# pedalElectricalDrawings.net
KiCad netlist of a schematic drawn in EAGLE
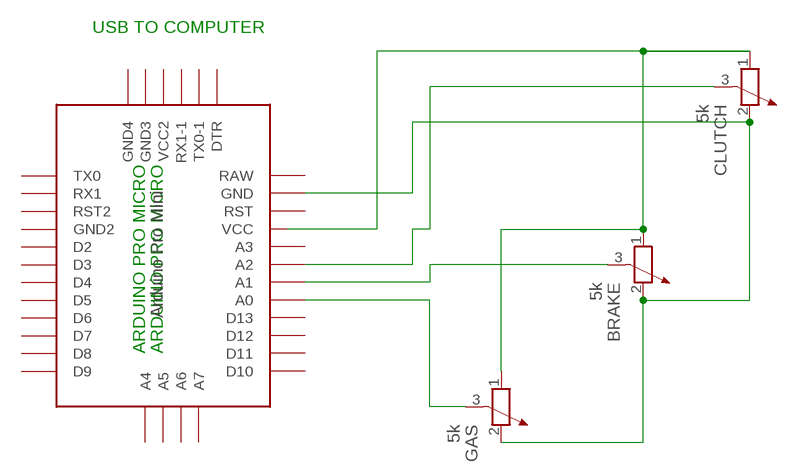
[diagram p0: schematic, sheet 1]

(export (version "E")
  (design (tool "Eeschema 10.0.6"))
  (components
    (comp (ref "BRAKE")
      (value "5k")
      (footprint "eagle-import:PT-10")
      (libsource (lib "eagle-import") (part "POTENTIOMETER_PT-10"))
    )
    (comp (ref "CLUTCH")
      (value "5k")
      (footprint "eagle-import:PT-10")
      (libsource (lib "eagle-import") (part "POTENTIOMETER_PT-10"))
    )
    (comp (ref "GAS")
      (value "5k")
      (footprint "eagle-import:PT-10")
      (libsource (lib "eagle-import") (part "POTENTIOMETER_PT-10"))
    )
    (comp (ref "U$1")
      (value "PRO-MINI")
      (footprint "eagle-import:PRO-MINI")
      (libsource (lib "eagle-import") (part "PRO-MINI"))
    )
  )
  (nets
    (net (code "1") (name "/RAW") (class "Default")
      (node (ref "U$1") (pin "RAW") (pinfunction "RAW_RAW") (pintype "power_in"))
    )
    (net (code "2") (name "Net-(BRAKE-Pad1)") (class "Default")
      (node (ref "BRAKE") (pin "1") (pinfunction "1_1") (pintype "passive"))
      (node (ref "CLUTCH") (pin "1") (pinfunction "1_1") (pintype "passive"))
      (node (ref "GAS") (pin "1") (pinfunction "1_1") (pintype "passive"))
    )
    (net (code "3") (name "Net-(BRAKE-Pad2)") (class "Default")
      (node (ref "BRAKE") (pin "2") (pinfunction "2_2") (pintype "passive"))
      (node (ref "CLUTCH") (pin "2") (pinfunction "2_2") (pintype "passive"))
      (node (ref "GAS") (pin "2") (pinfunction "2_2") (pintype "passive"))
      (node (ref "U$1") (pin "GND") (pinfunction "GND_GND") (pintype "input"))
    )
    (net (code "4") (name "Net-(BRAKE-Pad3)") (class "Default")
      (node (ref "BRAKE") (pin "3") (pinfunction "3_3") (pintype "passive"))
      (node (ref "U$1") (pin "A1") (pinfunction "A1_A1") (pintype "bidirectional"))
    )
    (net (code "5") (name "Net-(CLUTCH-Pad3)") (class "Default")
      (node (ref "CLUTCH") (pin "3") (pinfunction "3_3") (pintype "passive"))
      (node (ref "U$1") (pin "A2") (pinfunction "A2_A2") (pintype "bidirectional"))
    )
    (net (code "6") (name "Net-(GAS-Pad3)") (class "Default")
      (node (ref "GAS") (pin "3") (pinfunction "3_3") (pintype "passive"))
      (node (ref "U$1") (pin "A0") (pinfunction "A0_A0") (pintype "bidirectional"))
    )
    (net (code "7") (name "unconnected-(U$1-GND2-PadGND1)") (class "Default")
      (node (ref "U$1") (pin "GND1") (pinfunction "GND2_GND1") (pintype "bidirectional"))
    )
    (net (code "8") (name "unconnected-(U$1-GND4-PadGND2)") (class "Default")
      (node (ref "U$1") (pin "GND2") (pinfunction "GND4_GND2") (pintype "bidirectional"))
    )
    (net (code "9") (name "unconnected-(U$1-PadA3)") (class "Default")
      (node (ref "U$1") (pin "A3") (pinfunction "A3_A3") (pintype "bidirectional"))
    )
    (net (code "10") (name "unconnected-(U$1-PadA4)") (class "Default")
      (node (ref "U$1") (pin "A4") (pinfunction "A4_A4") (pintype "bidirectional"))
    )
    (net (code "11") (name "unconnected-(U$1-PadA5)") (class "Default")
      (node (ref "U$1") (pin "A5") (pinfunction "A5_A5") (pintype "bidirectional"))
    )
    (net (code "12") (name "unconnected-(U$1-PadA6)") (class "Default")
      (node (ref "U$1") (pin "A6") (pinfunction "A6_A6") (pintype "bidirectional"))
    )
    (net (code "13") (name "unconnected-(U$1-PadA7)") (class "Default")
      (node (ref "U$1") (pin "A7") (pinfunction "A7_A7") (pintype "bidirectional"))
    )
    (net (code "14") (name "unconnected-(U$1-PadD2)") (class "Default")
      (node (ref "U$1") (pin "D2") (pinfunction "D2_D2") (pintype "bidirectional"))
    )
    (net (code "15") (name "unconnected-(U$1-PadD3)") (class "Default")
      (node (ref "U$1") (pin "D3") (pinfunction "D3_D3") (pintype "bidirectional"))
    )
    (net (code "16") (name "unconnected-(U$1-PadD4)") (class "Default")
      (node (ref "U$1") (pin "D4") (pinfunction "D4_D4") (pintype "bidirectional"))
    )
    (net (code "17") (name "unconnected-(U$1-PadD5)") (class "Default")
      (node (ref "U$1") (pin "D5") (pinfunction "D5_D5") (pintype "bidirectional"))
    )
    (net (code "18") (name "unconnected-(U$1-PadD6)") (class "Default")
      (node (ref "U$1") (pin "D6") (pinfunction "D6_D6") (pintype "bidirectional"))
    )
    (net (code "19") (name "unconnected-(U$1-PadD7)") (class "Default")
      (node (ref "U$1") (pin "D7") (pinfunction "D7_D7") (pintype "bidirectional"))
    )
    (net (code "20") (name "unconnected-(U$1-PadD8)") (class "Default")
      (node (ref "U$1") (pin "D8") (pinfunction "D8_D8") (pintype "bidirectional"))
    )
    (net (code "21") (name "unconnected-(U$1-PadD9)") (class "Default")
      (node (ref "U$1") (pin "D9") (pinfunction "D9_D9") (pintype "bidirectional"))
    )
    (net (code "22") (name "unconnected-(U$1-PadD10)") (class "Default")
      (node (ref "U$1") (pin "D10") (pinfunction "D10_D10") (pintype "bidirectional"))
    )
    (net (code "23") (name "unconnected-(U$1-PadD11)") (class "Default")
      (node (ref "U$1") (pin "D11") (pinfunction "D11_D11") (pintype "bidirectional"))
    )
    (net (code "24") (name "unconnected-(U$1-PadD12)") (class "Default")
      (node (ref "U$1") (pin "D12") (pinfunction "D12_D12") (pintype "bidirectional"))
    )
    (net (code "25") (name "unconnected-(U$1-PadD13)") (class "Default")
      (node (ref "U$1") (pin "D13") (pinfunction "D13_D13") (pintype "bidirectional"))
    )
    (net (code "26") (name "unconnected-(U$1-PadDTR)") (class "Default")
      (node (ref "U$1") (pin "DTR") (pinfunction "DTR_DTR") (pintype "bidirectional"))
    )
    (net (code "27") (name "unconnected-(U$1-PadGND3)") (class "Default")
      (node (ref "U$1") (pin "GND3") (pinfunction "GND3_GND3") (pintype "bidirectional"))
    )
    (net (code "28") (name "unconnected-(U$1-PadRST)") (class "Default")
      (node (ref "U$1") (pin "RST") (pinfunction "RST_RST") (pintype "bidirectional"))
    )
    (net (code "29") (name "unconnected-(U$1-PadRX1)") (class "Default")
      (node (ref "U$1") (pin "RX1") (pinfunction "RX1_RX1") (pintype "bidirectional"))
    )
    (net (code "30") (name "unconnected-(U$1-PadRX1-1)") (class "Default")
      (node (ref "U$1") (pin "RX1-1") (pinfunction "RX1-1_RX1-1") (pintype "bidirectional"))
    )
    (net (code "31") (name "unconnected-(U$1-PadTX0)") (class "Default")
      (node (ref "U$1") (pin "TX0") (pinfunction "TX0_TX0") (pintype "bidirectional"))
    )
    (net (code "32") (name "unconnected-(U$1-PadTX0-1)") (class "Default")
      (node (ref "U$1") (pin "TX0-1") (pinfunction "TX0-1_TX0-1") (pintype "bidirectional"))
    )
    (net (code "33") (name "unconnected-(U$1-PadVCC)") (class "Default")
      (node (ref "U$1") (pin "VCC") (pinfunction "VCC_VCC") (pintype "bidirectional"))
    )
    (net (code "34") (name "unconnected-(U$1-RST2-PadRST1)") (class "Default")
      (node (ref "U$1") (pin "RST1") (pinfunction "RST2_RST1") (pintype "bidirectional"))
    )
    (net (code "35") (name "unconnected-(U$1-VCC2-PadVCC1)") (class "Default")
      (node (ref "U$1") (pin "VCC1") (pinfunction "VCC2_VCC1") (pintype "bidirectional"))
    )
  )
)
